# TF.net
KiCad netlist of a schematic drawn in Altium Designer
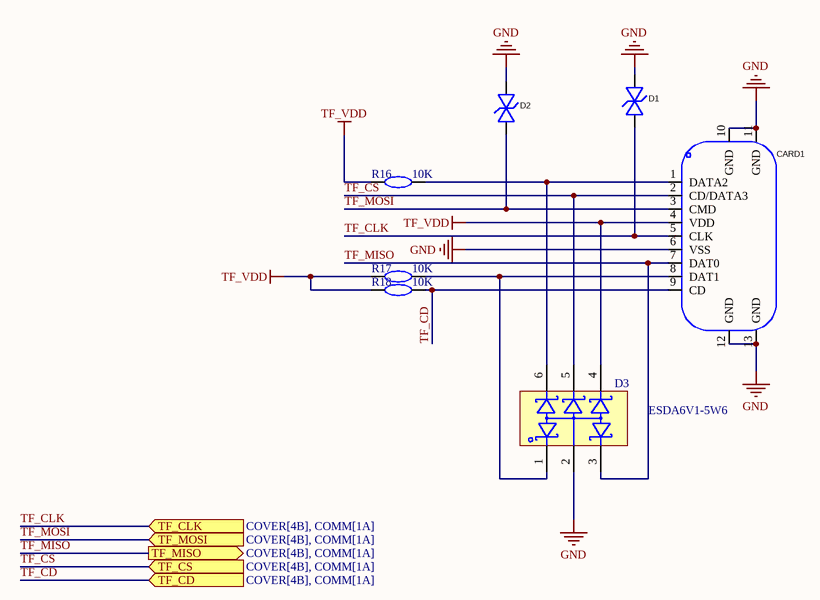
[diagram p0: TF.SchDoc]

(export (version "E")
  (design (tool "Eeschema 10.0.6"))
  (components
    (comp (ref "CARD1")
      (value "TF-115-BCP9")
      (footprint "TF-SMD_TF-115-BCP9")
      (fields (field (name "MANUFACTURER") "XUNPU(讯普)"))
      (libsource (lib "TF-115-BCP91_TF-115-BCP9") (part "TF-115-BCP9"))
    )
    (comp (ref "D1")
      (value "DESD3V3S1BL-7B")
      (footprint "X1-DFN1006-2_L1.0-W0.6-BI")
      (fields (field (name "MANUFACTURER") "DIODES(美台)"))
      (libsource (lib "DESD3V3S1BL-7B1_DESD3V3S1BL-7B") (part "DESD3V3S1BL-7B"))
    )
    (comp (ref "D2")
      (value "DESD3V3S1BL-7B")
      (footprint "X1-DFN1006-2_L1.0-W0.6-BI")
      (fields (field (name "MANUFACTURER") "DIODES(美台)"))
      (libsource (lib "DESD3V3S1BL-7B1_DESD3V3S1BL-7B") (part "DESD3V3S1BL-7B"))
    )
    (comp (ref "D3")
      (value "ESDA6V1-5W6")
      (footprint "SOT323-6L_L2.0-W1.3-LS2.1-BR")
      (description "C87908")
      (fields (field (name "MANUFACTURER") "ST(意法半导体)"))
      (libsource (lib "1-6TVS静电放电ESD") (part "ESDA6V1-5W6"))
    )
    (comp (ref "R16")
      (value "10K")
      (footprint "R0402")
      (fields (field (name "NAME") "10K"))
      (libsource (lib "my_library") (part "Res_0402"))
    )
    (comp (ref "R17")
      (value "10K")
      (footprint "R0402")
      (fields (field (name "NAME") "10K"))
      (libsource (lib "my_library") (part "Res_0402"))
    )
    (comp (ref "R18")
      (value "10K")
      (footprint "R0402")
      (fields (field (name "NAME") "10K"))
      (libsource (lib "my_library") (part "Res_0402"))
    )
  )
  (nets
    (net (code "1") (name "/TF_CD") (class "Default")
      (node (ref "CARD1") (pin "9") (pinfunction "CD_9") (pintype "passive"))
      (node (ref "R18") (pin "2") (pinfunction "2_2") (pintype "passive"))
    )
    (net (code "2") (name "/TF_CLK") (class "Default")
      (node (ref "CARD1") (pin "5") (pinfunction "CLK_5") (pintype "passive"))
      (node (ref "D1") (pin "1") (pinfunction "1_1") (pintype "passive"))
    )
    (net (code "3") (name "/TF_CS") (class "Default")
      (node (ref "CARD1") (pin "2") (pinfunction "CD/DATA3_2") (pintype "passive"))
      (node (ref "D3") (pin "5") (pinfunction "5_5") (pintype "passive"))
    )
    (net (code "4") (name "/TF_MISO") (class "Default")
      (node (ref "CARD1") (pin "7") (pinfunction "DAT0_7") (pintype "passive"))
      (node (ref "D3") (pin "3") (pinfunction "3_3") (pintype "passive"))
    )
    (net (code "5") (name "/TF_MOSI") (class "Default")
      (node (ref "CARD1") (pin "3") (pinfunction "CMD_3") (pintype "passive"))
      (node (ref "D2") (pin "1") (pinfunction "1_1") (pintype "passive"))
    )
    (net (code "6") (name "GND") (class "Default")
      (node (ref "CARD1") (pin "10") (pinfunction "GND_10") (pintype "passive"))
      (node (ref "CARD1") (pin "11") (pinfunction "GND_11") (pintype "passive"))
      (node (ref "CARD1") (pin "12") (pinfunction "GND_12") (pintype "passive"))
      (node (ref "CARD1") (pin "13") (pinfunction "GND_13") (pintype "passive"))
      (node (ref "CARD1") (pin "6") (pinfunction "VSS_6") (pintype "passive"))
      (node (ref "D1") (pin "2") (pinfunction "2_2") (pintype "passive"))
      (node (ref "D2") (pin "2") (pinfunction "2_2") (pintype "passive"))
      (node (ref "D3") (pin "2") (pinfunction "2_2") (pintype "passive"))
    )
    (net (code "7") (name "Net-(CARD1-DAT1)") (class "Default")
      (node (ref "CARD1") (pin "8") (pinfunction "DAT1_8") (pintype "passive"))
      (node (ref "D3") (pin "1") (pinfunction "1_1") (pintype "passive"))
      (node (ref "R17") (pin "2") (pinfunction "2_2") (pintype "passive"))
    )
    (net (code "8") (name "Net-(CARD1-DATA2)") (class "Default")
      (node (ref "CARD1") (pin "1") (pinfunction "DATA2_1") (pintype "passive"))
      (node (ref "D3") (pin "6") (pinfunction "6_6") (pintype "passive"))
      (node (ref "R16") (pin "2") (pinfunction "2_2") (pintype "passive"))
    )
    (net (code "9") (name "TF_VDD") (class "Default")
      (node (ref "CARD1") (pin "4") (pinfunction "VDD_4") (pintype "passive"))
      (node (ref "D3") (pin "4") (pinfunction "4_4") (pintype "passive"))
      (node (ref "R16") (pin "1") (pinfunction "1_1") (pintype "passive"))
      (node (ref "R17") (pin "1") (pinfunction "1_1") (pintype "passive"))
      (node (ref "R18") (pin "1") (pinfunction "1_1") (pintype "passive"))
    )
  )
)
